# UnidirectionalLevelShifiting.net
KiCad netlist of a schematic drawn in Altium Designer
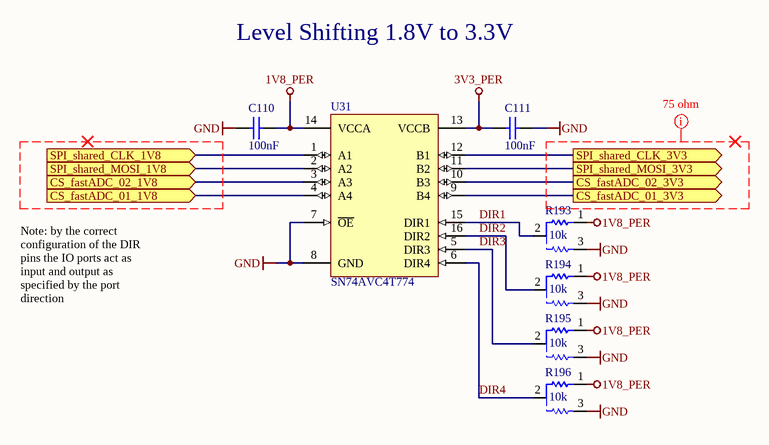
[diagram p0: UnidirectionalLevelShifiting.SchDoc]

(export (version "E")
  (design (tool "Eeschema 10.0.6"))
  (components
    (comp (ref "C110")
      (value "100nF")
      (footprint "C_0603(1608)100_L")
      (description "Capacitor 0603")
      (fields
        (field (name "TOLERANCE") "±10%")
        (field (name "VOLTAGE") "50V")
        (field (name "CREATED") "2018_09_13_AGeiger")
      )
      (libsource (lib "UltraZOhm_CarrierBoard") (part "C_0603"))
    )
    (comp (ref "C111")
      (value "100nF")
      (footprint "C_0603(1608)100_L")
      (description "Capacitor 0603")
      (fields
        (field (name "TOLERANCE") "±10%")
        (field (name "VOLTAGE") "50V")
        (field (name "CREATED") "2018_09_13_AGeiger")
      )
      (libsource (lib "UltraZOhm_CarrierBoard") (part "C_0603"))
    )
    (comp (ref "R193")
      (value "10k")
      (footprint "0603_Config")
      (fields
        (field (name "MPN") "MCWR06X1002FTL")
        (field (name "MF") "Multicomp")
        (field (name "VOLTAGE") "50V")
        (field (name "CREATED") "2018_09_04_AGeiger")
      )
      (libsource (lib "UltraZOhm_CarrierBoard") (part "R_config"))
    )
    (comp (ref "R194")
      (value "10k")
      (footprint "0603_Config")
      (fields
        (field (name "MPN") "MCWR06X1002FTL")
        (field (name "MF") "Multicomp")
        (field (name "VOLTAGE") "50V")
        (field (name "CREATED") "2018_09_04_AGeiger")
      )
      (libsource (lib "UltraZOhm_CarrierBoard") (part "R_config"))
    )
    (comp (ref "R195")
      (value "10k")
      (footprint "0603_Config")
      (fields
        (field (name "MPN") "MCWR06X1002FTL")
        (field (name "MF") "Multicomp")
        (field (name "VOLTAGE") "50V")
        (field (name "CREATED") "2018_09_04_AGeiger")
      )
      (libsource (lib "UltraZOhm_CarrierBoard") (part "R_config"))
    )
    (comp (ref "R196")
      (value "10k")
      (footprint "0603_Config")
      (fields
        (field (name "MPN") "MCWR06X1002FTL")
        (field (name "MF") "Multicomp")
        (field (name "VOLTAGE") "50V")
        (field (name "CREATED") "2018_09_04_AGeiger")
      )
      (libsource (lib "UltraZOhm_CarrierBoard") (part "R_config"))
    )
    (comp (ref "U31")
      (value "SN74AVC4T774")
      (footprint "QFN40P260X180X55-16N")
      (fields
        (field (name "MPN") "SN74AVC4T774RSVR")
        (field (name "MF") "Texas Instruments")
        (field (name "CREATED") "2018_09_13_AGeiger")
      )
      (libsource (lib "UltraZOhm_CarrierBoard") (part "SN74AVC4T774RSVR"))
    )
  )
  (nets
    (net (code "1") (name "/CS_fastADC_01_1V8") (class "Default")
      (node (ref "U31") (pin "4") (pinfunction "A4_4") (pintype "bidirectional"))
    )
    (net (code "2") (name "/CS_fastADC_01_3V3") (class "Default")
      (node (ref "U31") (pin "9") (pinfunction "B4_9") (pintype "bidirectional"))
    )
    (net (code "3") (name "/CS_fastADC_02_1V8") (class "Default")
      (node (ref "U31") (pin "3") (pinfunction "A3_3") (pintype "bidirectional"))
    )
    (net (code "4") (name "/CS_fastADC_02_3V3") (class "Default")
      (node (ref "U31") (pin "10") (pinfunction "B3_10") (pintype "bidirectional"))
    )
    (net (code "5") (name "/DIR1") (class "Default")
      (node (ref "R193") (pin "2") (pinfunction "2_2") (pintype "passive"))
      (node (ref "U31") (pin "15") (pinfunction "DIR1_15") (pintype "input"))
    )
    (net (code "6") (name "/DIR2") (class "Default")
      (node (ref "R194") (pin "2") (pinfunction "2_2") (pintype "passive"))
      (node (ref "U31") (pin "16") (pinfunction "DIR2_16") (pintype "input"))
    )
    (net (code "7") (name "/DIR3") (class "Default")
      (node (ref "R195") (pin "2") (pinfunction "2_2") (pintype "passive"))
      (node (ref "U31") (pin "5") (pinfunction "DIR3_5") (pintype "input"))
    )
    (net (code "8") (name "/DIR4") (class "Default")
      (node (ref "R196") (pin "2") (pinfunction "2_2") (pintype "passive"))
      (node (ref "U31") (pin "6") (pinfunction "DIR4_6") (pintype "input"))
    )
    (net (code "9") (name "/SPI_shared_CLK_1V8") (class "Default")
      (node (ref "U31") (pin "1") (pinfunction "A1_1") (pintype "bidirectional"))
    )
    (net (code "10") (name "/SPI_shared_CLK_3V3") (class "Default")
      (node (ref "U31") (pin "12") (pinfunction "B1_12") (pintype "bidirectional"))
    )
    (net (code "11") (name "/SPI_shared_MOSI_1V8") (class "Default")
      (node (ref "U31") (pin "2") (pinfunction "A2_2") (pintype "bidirectional"))
    )
    (net (code "12") (name "/SPI_shared_MOSI_3V3") (class "Default")
      (node (ref "U31") (pin "11") (pinfunction "B2_11") (pintype "bidirectional"))
    )
    (net (code "13") (name "1V8_PER") (class "Default")
      (node (ref "C110") (pin "1") (pinfunction "1_1") (pintype "passive"))
      (node (ref "R193") (pin "1") (pinfunction "1_1") (pintype "passive"))
      (node (ref "R194") (pin "1") (pinfunction "1_1") (pintype "passive"))
      (node (ref "R195") (pin "1") (pinfunction "1_1") (pintype "passive"))
      (node (ref "R196") (pin "1") (pinfunction "1_1") (pintype "passive"))
      (node (ref "U31") (pin "14") (pinfunction "VCCA_14") (pintype "power_in"))
    )
    (net (code "14") (name "3V3_PER") (class "Default")
      (node (ref "C111") (pin "2") (pinfunction "2_2") (pintype "passive"))
      (node (ref "U31") (pin "13") (pinfunction "VCCB_13") (pintype "power_in"))
    )
    (net (code "15") (name "GND") (class "Default")
      (node (ref "C110") (pin "2") (pinfunction "2_2") (pintype "passive"))
      (node (ref "C111") (pin "1") (pinfunction "1_1") (pintype "passive"))
      (node (ref "R193") (pin "3") (pinfunction "3_3") (pintype "passive"))
      (node (ref "R194") (pin "3") (pinfunction "3_3") (pintype "passive"))
      (node (ref "R195") (pin "3") (pinfunction "3_3") (pintype "passive"))
      (node (ref "R196") (pin "3") (pinfunction "3_3") (pintype "passive"))
      (node (ref "U31") (pin "7") (pinfunction "~{OE}_7") (pintype "input"))
      (node (ref "U31") (pin "8") (pinfunction "GND_8") (pintype "power_in"))
    )
  )
)
